# Sheet1.net
KiCad netlist of a schematic drawn in Altium Designer
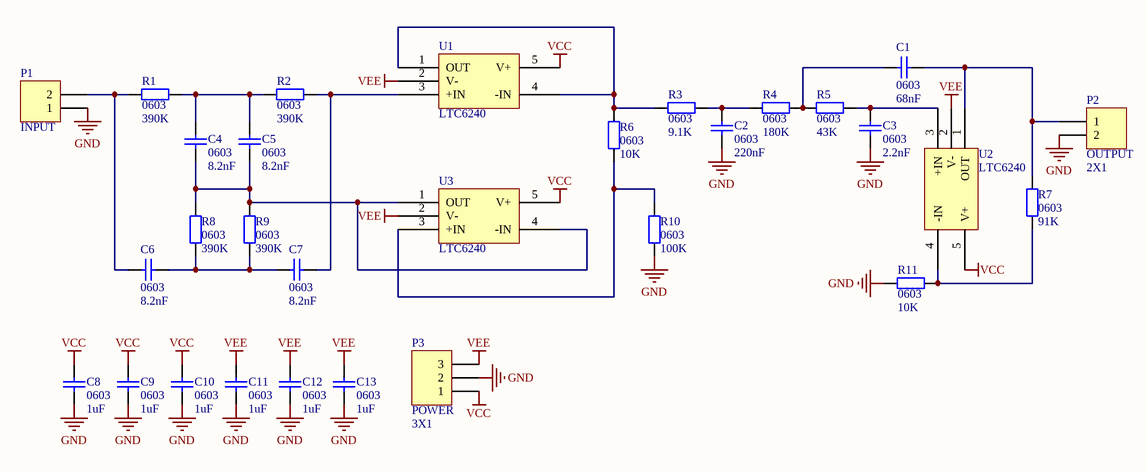
[diagram p0: Sheet1.SchDoc]

(export (version "E")
  (design (tool "Eeschema 10.0.6"))
  (components
    (comp (ref "C1")
      (value "0603")
      (footprint "J1-0603")
      (description "Capacitor")
      (fields (field (name "ALTIUM_VALUE") "68nF"))
      (libsource (lib "Miscellaneous Devices Local Copy") (part "Cap"))
    )
    (comp (ref "C2")
      (value "0603")
      (footprint "J1-0603")
      (description "Capacitor")
      (fields (field (name "ALTIUM_VALUE") "220nF"))
      (libsource (lib "Miscellaneous Devices Local Copy") (part "Cap"))
    )
    (comp (ref "C3")
      (value "0603")
      (footprint "J1-0603")
      (description "Capacitor")
      (fields (field (name "ALTIUM_VALUE") "2.2nF"))
      (libsource (lib "Miscellaneous Devices Local Copy") (part "Cap"))
    )
    (comp (ref "C4")
      (value "0603")
      (footprint "J1-0603")
      (description "Capacitor")
      (fields (field (name "ALTIUM_VALUE") "8.2nF"))
      (libsource (lib "Miscellaneous Devices Local Copy") (part "Cap"))
    )
    (comp (ref "C5")
      (value "0603")
      (footprint "J1-0603")
      (description "Capacitor")
      (fields (field (name "ALTIUM_VALUE") "8.2nF"))
      (libsource (lib "Miscellaneous Devices Local Copy") (part "Cap"))
    )
    (comp (ref "C6")
      (value "0603")
      (footprint "J1-0603")
      (description "Capacitor")
      (fields (field (name "ALTIUM_VALUE") "8.2nF"))
      (libsource (lib "Miscellaneous Devices Local Copy") (part "Cap"))
    )
    (comp (ref "C7")
      (value "0603")
      (footprint "J1-0603")
      (description "Capacitor")
      (fields (field (name "ALTIUM_VALUE") "8.2nF"))
      (libsource (lib "Miscellaneous Devices Local Copy") (part "Cap"))
    )
    (comp (ref "C8")
      (value "0603")
      (footprint "J1-0603")
      (description "Capacitor")
      (fields (field (name "ALTIUM_VALUE") "1uF"))
      (libsource (lib "Miscellaneous Devices Local Copy") (part "Cap"))
    )
    (comp (ref "C9")
      (value "0603")
      (footprint "J1-0603")
      (description "Capacitor")
      (fields (field (name "ALTIUM_VALUE") "1uF"))
      (libsource (lib "Miscellaneous Devices Local Copy") (part "Cap"))
    )
    (comp (ref "C10")
      (value "0603")
      (footprint "J1-0603")
      (description "Capacitor")
      (fields (field (name "ALTIUM_VALUE") "1uF"))
      (libsource (lib "Miscellaneous Devices Local Copy") (part "Cap"))
    )
    (comp (ref "C11")
      (value "0603")
      (footprint "J1-0603")
      (description "Capacitor")
      (fields (field (name "ALTIUM_VALUE") "1uF"))
      (libsource (lib "Miscellaneous Devices Local Copy") (part "Cap"))
    )
    (comp (ref "C12")
      (value "0603")
      (footprint "J1-0603")
      (description "Capacitor")
      (fields (field (name "ALTIUM_VALUE") "1uF"))
      (libsource (lib "Miscellaneous Devices Local Copy") (part "Cap"))
    )
    (comp (ref "C13")
      (value "0603")
      (footprint "J1-0603")
      (description "Capacitor")
      (fields (field (name "ALTIUM_VALUE") "1uF"))
      (libsource (lib "Miscellaneous Devices Local Copy") (part "Cap"))
    )
    (comp (ref "P1")
      (value "INPUT")
      (footprint "HDR1X2")
      (description "Header, 2-Pin")
      (libsource (lib "Miscellaneous Connectors Local Copy") (part "Header 2"))
    )
    (comp (ref "P2")
      (value "OUTPUT")
      (footprint "HDR1X2")
      (description "Header, 2-Pin")
      (fields (field (name "ALTIUM_VALUE") "2X1"))
      (libsource (lib "") (part "Header 2_1"))
    )
    (comp (ref "P3")
      (value "POWER")
      (footprint "HDR1X3")
      (description "Header, 3-Pin")
      (fields (field (name "ALTIUM_VALUE") "3X1"))
      (libsource (lib "Miscellaneous Connectors Local Copy") (part "Header 3"))
    )
    (comp (ref "R1")
      (value "0603")
      (footprint "1608[0603]")
      (description "Resistor")
      (fields (field (name "ALTIUM_VALUE") "390K"))
      (libsource (lib "Miscellaneous Devices Local Copy") (part "Res2"))
    )
    (comp (ref "R2")
      (value "0603")
      (footprint "1608[0603]")
      (description "Resistor")
      (fields (field (name "ALTIUM_VALUE") "390K"))
      (libsource (lib "Miscellaneous Devices Local Copy") (part "Res2"))
    )
    (comp (ref "R3")
      (value "0603")
      (footprint "1608[0603]")
      (description "Resistor")
      (fields (field (name "ALTIUM_VALUE") "9.1K"))
      (libsource (lib "") (part "Res2_2"))
    )
    (comp (ref "R4")
      (value "0603")
      (footprint "1608[0603]")
      (description "Resistor")
      (fields (field (name "ALTIUM_VALUE") "180K"))
      (libsource (lib "") (part "Res2_2"))
    )
    (comp (ref "R5")
      (value "0603")
      (footprint "1608[0603]")
      (description "Resistor")
      (fields (field (name "ALTIUM_VALUE") "43K"))
      (libsource (lib "") (part "Res2_2"))
    )
    (comp (ref "R6")
      (value "0603")
      (footprint "1608[0603]")
      (description "Resistor")
      (fields (field (name "ALTIUM_VALUE") "10K"))
      (libsource (lib "") (part "Res2_3"))
    )
    (comp (ref "R7")
      (value "0603")
      (footprint "1608[0603]")
      (description "Resistor")
      (fields (field (name "ALTIUM_VALUE") "91K"))
      (libsource (lib "") (part "Res2_1"))
    )
    (comp (ref "R8")
      (value "0603")
      (footprint "1608[0603]")
      (description "Resistor")
      (fields (field (name "ALTIUM_VALUE") "390K"))
      (libsource (lib "") (part "Res2_1"))
    )
    (comp (ref "R9")
      (value "0603")
      (footprint "1608[0603]")
      (description "Resistor")
      (fields (field (name "ALTIUM_VALUE") "390K"))
      (libsource (lib "") (part "Res2_1"))
    )
    (comp (ref "R10")
      (value "0603")
      (footprint "1608[0603]")
      (description "Resistor")
      (fields (field (name "ALTIUM_VALUE") "100K"))
      (libsource (lib "") (part "Res2_1"))
    )
    (comp (ref "R11")
      (value "0603")
      (footprint "1608[0603]")
      (description "Resistor")
      (fields (field (name "ALTIUM_VALUE") "10K"))
      (libsource (lib "Miscellaneous Devices Local Copy") (part "Res2"))
    )
    (comp (ref "U1")
      (value "LTC6240")
      (footprint "LTC6240_SOT23")
      (description "low noise jfet opamp")
      (libsource (lib "") (part "LTC6240_1"))
    )
    (comp (ref "U2")
      (value "LTC6240")
      (footprint "LTC6240_SOT23")
      (description "low noise jfet opamp")
      (libsource (lib "Schlib1") (part "LTC6240"))
    )
    (comp (ref "U3")
      (value "LTC6240")
      (footprint "LTC6240_SOT23")
      (description "low noise jfet opamp")
      (libsource (lib "") (part "LTC6240_1"))
    )
  )
  (nets
    (net (code "1") (name "GND") (class "Default")
      (node (ref "C10") (pin "2") (pinfunction "2_2") (pintype "passive"))
      (node (ref "C11") (pin "2") (pinfunction "2_2") (pintype "passive"))
      (node (ref "C12") (pin "2") (pinfunction "2_2") (pintype "passive"))
      (node (ref "C13") (pin "2") (pinfunction "2_2") (pintype "passive"))
      (node (ref "C2") (pin "1") (pinfunction "1_1") (pintype "passive"))
      (node (ref "C3") (pin "1") (pinfunction "1_1") (pintype "passive"))
      (node (ref "C8") (pin "2") (pinfunction "2_2") (pintype "passive"))
      (node (ref "C9") (pin "2") (pinfunction "2_2") (pintype "passive"))
      (node (ref "P1") (pin "1") (pinfunction "1_1") (pintype "passive"))
      (node (ref "P2") (pin "2") (pinfunction "2_2") (pintype "passive"))
      (node (ref "P3") (pin "2") (pinfunction "2_2") (pintype "passive"))
      (node (ref "R10") (pin "2") (pinfunction "2_2") (pintype "passive"))
      (node (ref "R11") (pin "1") (pinfunction "1_1") (pintype "passive"))
    )
    (net (code "2") (name "Net-(C1-Pad2)") (class "Default")
      (node (ref "C1") (pin "2") (pinfunction "2_2") (pintype "passive"))
      (node (ref "R4") (pin "1") (pinfunction "1_1") (pintype "passive"))
      (node (ref "R5") (pin "2") (pinfunction "2_2") (pintype "passive"))
    )
    (net (code "3") (name "Net-(C2-Pad2)") (class "Default")
      (node (ref "C2") (pin "2") (pinfunction "2_2") (pintype "passive"))
      (node (ref "R3") (pin "1") (pinfunction "1_1") (pintype "passive"))
      (node (ref "R4") (pin "2") (pinfunction "2_2") (pintype "passive"))
    )
    (net (code "4") (name "Net-(C4-Pad2)") (class "Default")
      (node (ref "C4") (pin "2") (pinfunction "2_2") (pintype "passive"))
      (node (ref "C5") (pin "2") (pinfunction "2_2") (pintype "passive"))
      (node (ref "R1") (pin "2") (pinfunction "2_2") (pintype "passive"))
      (node (ref "R2") (pin "1") (pinfunction "1_1") (pintype "passive"))
    )
    (net (code "5") (name "Net-(C6-Pad1)") (class "Default")
      (node (ref "C6") (pin "1") (pinfunction "1_1") (pintype "passive"))
      (node (ref "C7") (pin "2") (pinfunction "2_2") (pintype "passive"))
      (node (ref "R8") (pin "2") (pinfunction "2_2") (pintype "passive"))
      (node (ref "R9") (pin "2") (pinfunction "2_2") (pintype "passive"))
    )
    (net (code "6") (name "Net-(C6-Pad2)") (class "Default")
      (node (ref "C6") (pin "2") (pinfunction "2_2") (pintype "passive"))
      (node (ref "P1") (pin "2") (pinfunction "2_2") (pintype "passive"))
      (node (ref "R1") (pin "1") (pinfunction "1_1") (pintype "passive"))
    )
    (net (code "7") (name "Net-(U1-+IN)") (class "Default")
      (node (ref "C7") (pin "1") (pinfunction "1_1") (pintype "passive"))
      (node (ref "R2") (pin "2") (pinfunction "2_2") (pintype "passive"))
      (node (ref "U1") (pin "3") (pinfunction "+IN_3") (pintype "passive"))
    )
    (net (code "8") (name "Net-(U1--IN)") (class "Default")
      (node (ref "R3") (pin "2") (pinfunction "2_2") (pintype "passive"))
      (node (ref "R6") (pin "2") (pinfunction "2_2") (pintype "passive"))
      (node (ref "U1") (pin "1") (pinfunction "OUT_1") (pintype "passive"))
      (node (ref "U1") (pin "4") (pinfunction "-IN_4") (pintype "passive"))
    )
    (net (code "9") (name "Net-(U2-+IN)") (class "Default")
      (node (ref "C3") (pin "2") (pinfunction "2_2") (pintype "passive"))
      (node (ref "R5") (pin "1") (pinfunction "1_1") (pintype "passive"))
      (node (ref "U2") (pin "3") (pinfunction "+IN_3") (pintype "passive"))
    )
    (net (code "10") (name "Net-(U2--IN)") (class "Default")
      (node (ref "R11") (pin "2") (pinfunction "2_2") (pintype "passive"))
      (node (ref "R7") (pin "2") (pinfunction "2_2") (pintype "passive"))
      (node (ref "U2") (pin "4") (pinfunction "-IN_4") (pintype "passive"))
    )
    (net (code "11") (name "Net-(U2-OUT)") (class "Default")
      (node (ref "C1") (pin "1") (pinfunction "1_1") (pintype "passive"))
      (node (ref "P2") (pin "1") (pinfunction "1_1") (pintype "passive"))
      (node (ref "R7") (pin "1") (pinfunction "1_1") (pintype "passive"))
      (node (ref "U2") (pin "1") (pinfunction "OUT_1") (pintype "passive"))
    )
    (net (code "12") (name "Net-(U3-+IN)") (class "Default")
      (node (ref "R10") (pin "1") (pinfunction "1_1") (pintype "passive"))
      (node (ref "R6") (pin "1") (pinfunction "1_1") (pintype "passive"))
      (node (ref "U3") (pin "3") (pinfunction "+IN_3") (pintype "passive"))
    )
    (net (code "13") (name "Net-(U3--IN)") (class "Default")
      (node (ref "C4") (pin "1") (pinfunction "1_1") (pintype "passive"))
      (node (ref "C5") (pin "1") (pinfunction "1_1") (pintype "passive"))
      (node (ref "R8") (pin "1") (pinfunction "1_1") (pintype "passive"))
      (node (ref "R9") (pin "1") (pinfunction "1_1") (pintype "passive"))
      (node (ref "U3") (pin "1") (pinfunction "OUT_1") (pintype "passive"))
      (node (ref "U3") (pin "4") (pinfunction "-IN_4") (pintype "passive"))
    )
    (net (code "14") (name "VCC") (class "Default")
      (node (ref "C10") (pin "1") (pinfunction "1_1") (pintype "passive"))
      (node (ref "C8") (pin "1") (pinfunction "1_1") (pintype "passive"))
      (node (ref "C9") (pin "1") (pinfunction "1_1") (pintype "passive"))
      (node (ref "P3") (pin "1") (pinfunction "1_1") (pintype "passive"))
      (node (ref "U1") (pin "5") (pinfunction "V+_5") (pintype "passive"))
      (node (ref "U2") (pin "5") (pinfunction "V+_5") (pintype "passive"))
      (node (ref "U3") (pin "5") (pinfunction "V+_5") (pintype "passive"))
    )
    (net (code "15") (name "VEE") (class "Default")
      (node (ref "C11") (pin "1") (pinfunction "1_1") (pintype "passive"))
      (node (ref "C12") (pin "1") (pinfunction "1_1") (pintype "passive"))
      (node (ref "C13") (pin "1") (pinfunction "1_1") (pintype "passive"))
      (node (ref "P3") (pin "3") (pinfunction "3_3") (pintype "passive"))
      (node (ref "U1") (pin "2") (pinfunction "V-_2") (pintype "passive"))
      (node (ref "U2") (pin "2") (pinfunction "V-_2") (pintype "passive"))
      (node (ref "U3") (pin "2") (pinfunction "V-_2") (pintype "passive"))
    )
  )
)
